# Delta_Calc.net
KiCad netlist of a schematic drawn in EAGLE
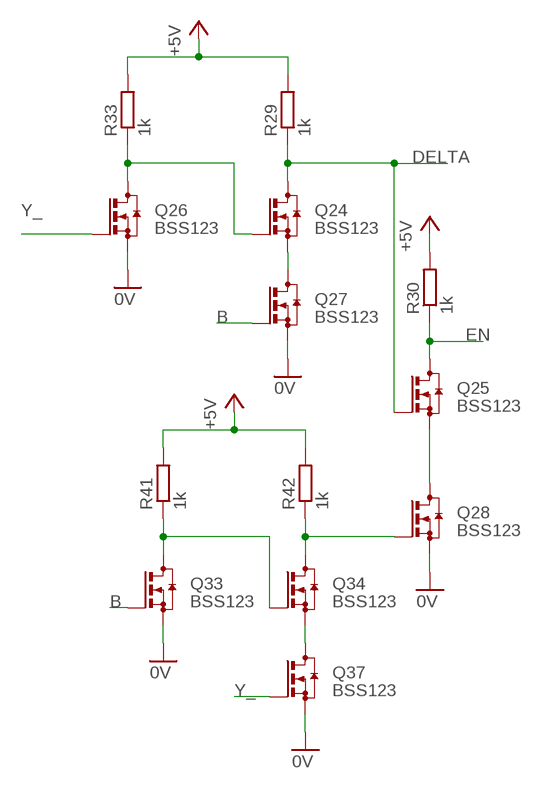
[diagram p0: schematic, sheet 1]

(export (version "E")
  (design (tool "Eeschema 10.0.6"))
  (components
    (comp (ref "Q24")
      (value "BSS123")
      (footprint "eagle-import:SOT23")
      (libsource (lib "eagle-import") (part "BSS123"))
    )
    (comp (ref "Q25")
      (value "BSS123")
      (footprint "eagle-import:SOT23")
      (libsource (lib "eagle-import") (part "BSS123"))
    )
    (comp (ref "Q26")
      (value "BSS123")
      (footprint "eagle-import:SOT23")
      (libsource (lib "eagle-import") (part "BSS123"))
    )
    (comp (ref "Q27")
      (value "BSS123")
      (footprint "eagle-import:SOT23")
      (libsource (lib "eagle-import") (part "BSS123"))
    )
    (comp (ref "Q28")
      (value "BSS123")
      (footprint "eagle-import:SOT23")
      (libsource (lib "eagle-import") (part "BSS123"))
    )
    (comp (ref "Q33")
      (value "BSS123")
      (footprint "eagle-import:SOT23")
      (libsource (lib "eagle-import") (part "BSS123"))
    )
    (comp (ref "Q34")
      (value "BSS123")
      (footprint "eagle-import:SOT23")
      (libsource (lib "eagle-import") (part "BSS123"))
    )
    (comp (ref "Q37")
      (value "BSS123")
      (footprint "eagle-import:SOT23")
      (libsource (lib "eagle-import") (part "BSS123"))
    )
    (comp (ref "R29")
      (value "1k")
      (footprint "eagle-import:M0805")
      (libsource (lib "eagle-import") (part "R-EU_M0805"))
    )
    (comp (ref "R30")
      (value "1k")
      (footprint "eagle-import:M0805")
      (libsource (lib "eagle-import") (part "R-EU_M0805"))
    )
    (comp (ref "R33")
      (value "1k")
      (footprint "eagle-import:M0805")
      (libsource (lib "eagle-import") (part "R-EU_M0805"))
    )
    (comp (ref "R41")
      (value "1k")
      (footprint "eagle-import:M0805")
      (libsource (lib "eagle-import") (part "R-EU_M0805"))
    )
    (comp (ref "R42")
      (value "1k")
      (footprint "eagle-import:M0805")
      (libsource (lib "eagle-import") (part "R-EU_M0805"))
    )
  )
  (nets
    (net (code "1") (name "+5V") (class "Default")
      (node (ref "R29") (pin "2") (pinfunction "2_2") (pintype "passive"))
      (node (ref "R30") (pin "2") (pinfunction "2_2") (pintype "passive"))
      (node (ref "R33") (pin "2") (pinfunction "2_2") (pintype "passive"))
      (node (ref "R41") (pin "2") (pinfunction "2_2") (pintype "passive"))
      (node (ref "R42") (pin "2") (pinfunction "2_2") (pintype "passive"))
    )
    (net (code "2") (name "/B") (class "Default")
      (node (ref "Q27") (pin "1") (pinfunction "G_1") (pintype "passive"))
      (node (ref "Q33") (pin "1") (pinfunction "G_1") (pintype "passive"))
    )
    (net (code "3") (name "/DELTA") (class "Default")
      (node (ref "Q24") (pin "3") (pinfunction "D_3") (pintype "passive"))
      (node (ref "Q25") (pin "1") (pinfunction "G_1") (pintype "passive"))
      (node (ref "R29") (pin "1") (pinfunction "1_1") (pintype "passive"))
    )
    (net (code "4") (name "/EN") (class "Default")
      (node (ref "Q25") (pin "3") (pinfunction "D_3") (pintype "passive"))
      (node (ref "R30") (pin "1") (pinfunction "1_1") (pintype "passive"))
    )
    (net (code "5") (name "/Y_") (class "Default")
      (node (ref "Q26") (pin "1") (pinfunction "G_1") (pintype "passive"))
      (node (ref "Q37") (pin "1") (pinfunction "G_1") (pintype "passive"))
    )
    (net (code "6") (name "0V") (class "Default")
      (node (ref "Q26") (pin "2") (pinfunction "S_2") (pintype "passive"))
      (node (ref "Q27") (pin "2") (pinfunction "S_2") (pintype "passive"))
      (node (ref "Q28") (pin "2") (pinfunction "S_2") (pintype "passive"))
      (node (ref "Q33") (pin "2") (pinfunction "S_2") (pintype "passive"))
      (node (ref "Q37") (pin "2") (pinfunction "S_2") (pintype "passive"))
    )
    (net (code "7") (name "Net-(Q24-G)") (class "Default")
      (node (ref "Q24") (pin "1") (pinfunction "G_1") (pintype "passive"))
      (node (ref "Q26") (pin "3") (pinfunction "D_3") (pintype "passive"))
      (node (ref "R33") (pin "1") (pinfunction "1_1") (pintype "passive"))
    )
    (net (code "8") (name "Net-(Q24-S)") (class "Default")
      (node (ref "Q24") (pin "2") (pinfunction "S_2") (pintype "passive"))
      (node (ref "Q27") (pin "3") (pinfunction "D_3") (pintype "passive"))
    )
    (net (code "9") (name "Net-(Q25-S)") (class "Default")
      (node (ref "Q25") (pin "2") (pinfunction "S_2") (pintype "passive"))
      (node (ref "Q28") (pin "3") (pinfunction "D_3") (pintype "passive"))
    )
    (net (code "10") (name "Net-(Q28-G)") (class "Default")
      (node (ref "Q28") (pin "1") (pinfunction "G_1") (pintype "passive"))
      (node (ref "Q34") (pin "3") (pinfunction "D_3") (pintype "passive"))
      (node (ref "R42") (pin "1") (pinfunction "1_1") (pintype "passive"))
    )
    (net (code "11") (name "Net-(Q33-D)") (class "Default")
      (node (ref "Q33") (pin "3") (pinfunction "D_3") (pintype "passive"))
      (node (ref "Q34") (pin "1") (pinfunction "G_1") (pintype "passive"))
      (node (ref "R41") (pin "1") (pinfunction "1_1") (pintype "passive"))
    )
    (net (code "12") (name "Net-(Q34-S)") (class "Default")
      (node (ref "Q34") (pin "2") (pinfunction "S_2") (pintype "passive"))
      (node (ref "Q37") (pin "3") (pinfunction "D_3") (pintype "passive"))
    )
  )
)
